# GBprinter-D1-Shield.net
KiCad netlist of a schematic drawn in EAGLE
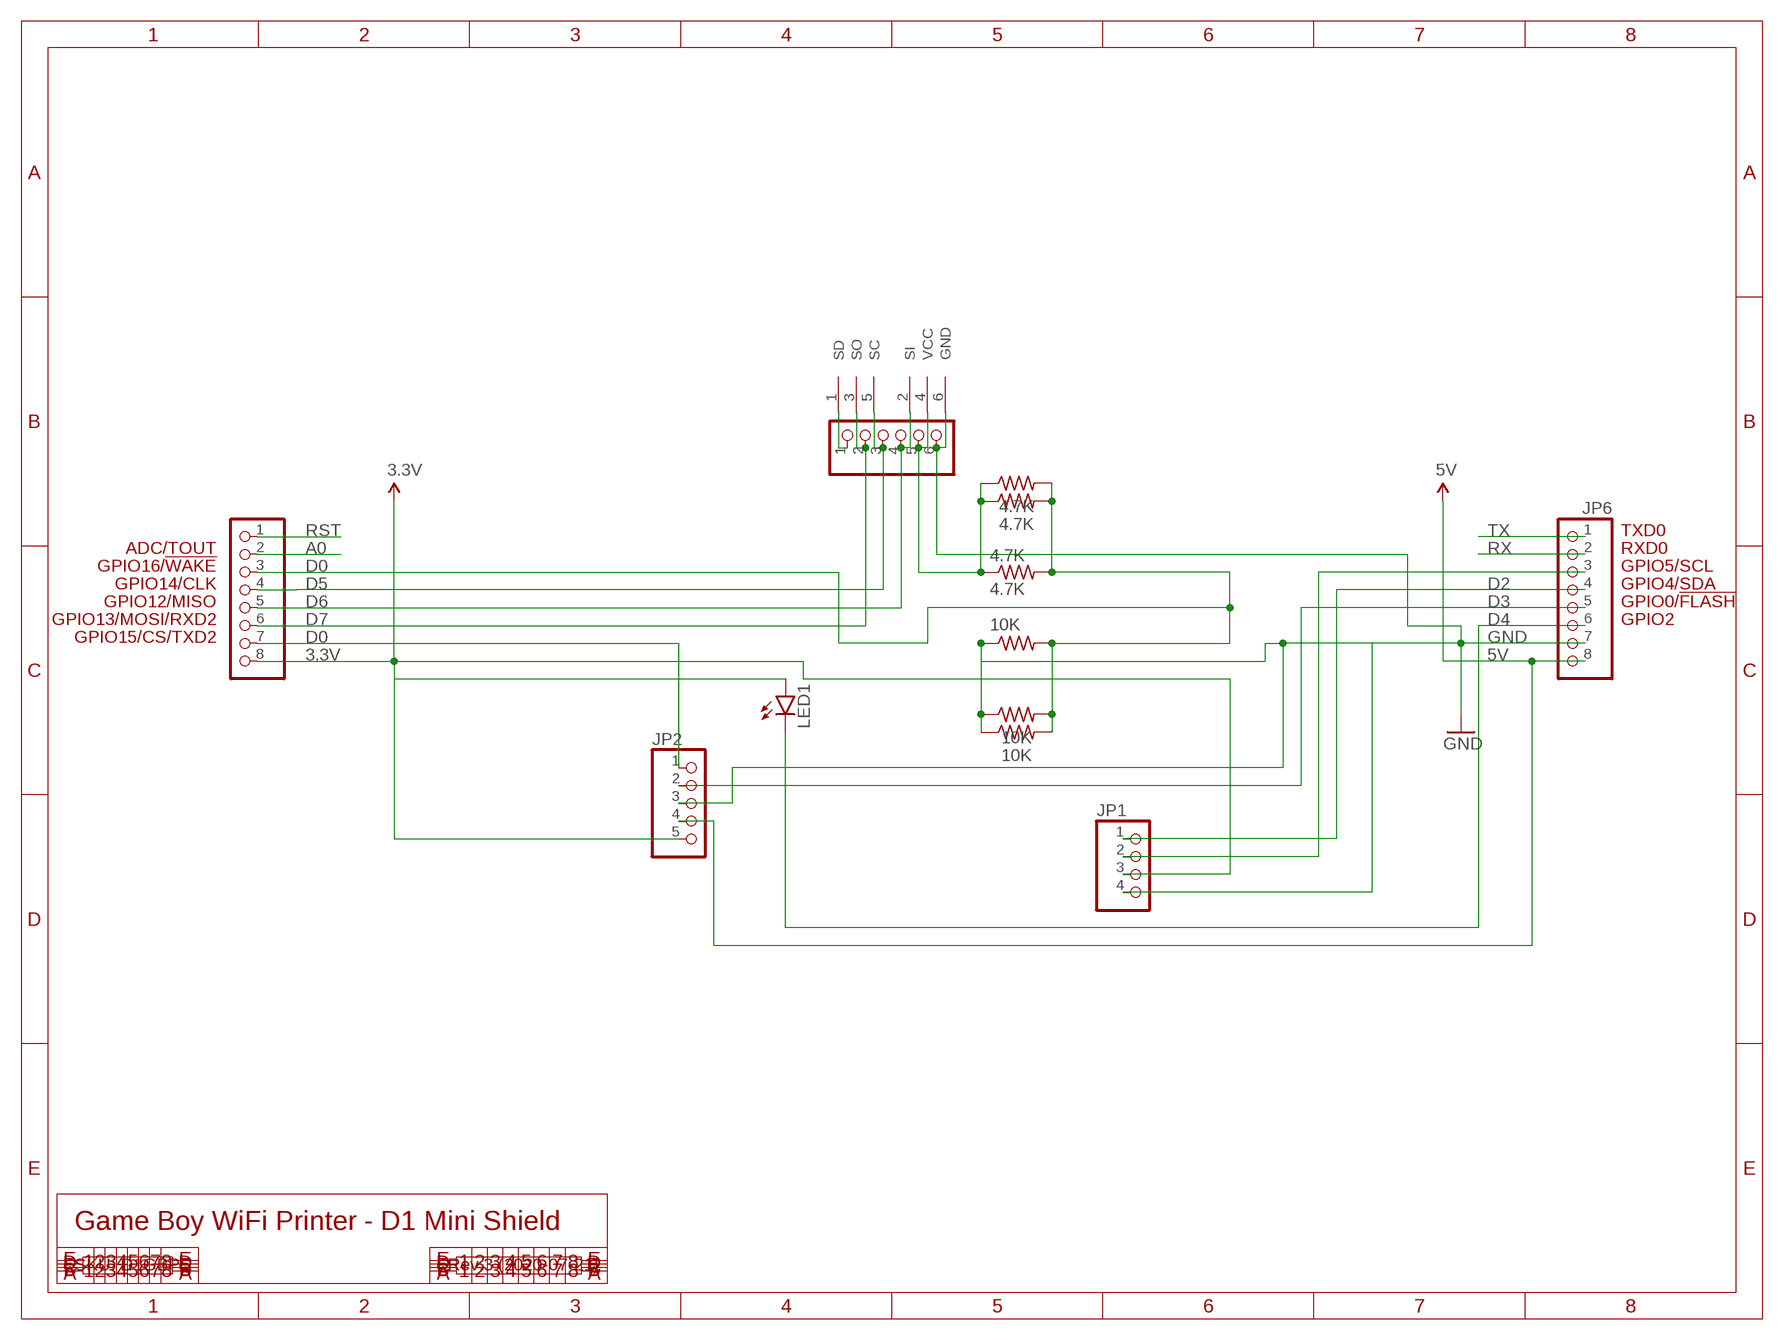
[diagram p0: schematic, sheet 1]

(export (version "E")
  (design (tool "Eeschema 10.0.6"))
  (components
    (comp (ref "4.7K")
      (value "4.7K")
      (footprint "eagle-import:0207_10")
      (libsource (lib "eagle-import") (part "R-US_0207/10"))
    )
    (comp (ref "10K")
      (value "10K")
      (footprint "eagle-import:0207_10")
      (libsource (lib "eagle-import") (part "R-US_0207/10"))
    )
    (comp (ref "JP1")
      (value "PINHD-1X4/OCT")
      (footprint "eagle-import:1X04_OCT")
      (libsource (lib "eagle-import") (part "PINHD-1X4/OCT"))
    )
    (comp (ref "JP2")
      (value "PINHD-1X5/OCT")
      (footprint "eagle-import:1X05_OCT")
      (libsource (lib "eagle-import") (part "PINHD-1X5/OCT"))
    )
    (comp (ref "JP3")
      (value "PINHD-1X8/OCT")
      (footprint "eagle-import:1X08_OCT")
      (libsource (lib "eagle-import") (part "PINHD-1X8/OCT"))
    )
    (comp (ref "JP4")
      (value "PINHD-1X6/OCT")
      (footprint "eagle-import:1X06_OCT")
      (libsource (lib "eagle-import") (part "PINHD-1X6/OCT"))
    )
    (comp (ref "JP6")
      (value "PINHD-1X8/OCT")
      (footprint "eagle-import:1X08_OCT")
      (libsource (lib "eagle-import") (part "PINHD-1X8/OCT"))
    )
    (comp (ref "LED1")
      (value "LED3MM")
      (footprint "eagle-import:LED3MM")
      (libsource (lib "eagle-import") (part "LED3MM"))
    )
    (comp (ref "R1")
      (value "4.7K")
      (footprint "eagle-import:RESC2012X65")
      (libsource (lib "eagle-import") (part "R-USCHIP-0805(2012-METRIC)_"))
    )
    (comp (ref "R2")
      (value "10K")
      (footprint "eagle-import:RESC2012X65")
      (libsource (lib "eagle-import") (part "R-USCHIP-0805(2012-METRIC)_"))
    )
    (comp (ref "R3")
      (value "10K")
      (footprint "eagle-import:RESC2012X65")
      (libsource (lib "eagle-import") (part "R-USCHIP-0805(2012-METRIC)_"))
    )
    (comp (ref "R5")
      (value "4.7K")
      (footprint "eagle-import:RESC2012X65")
      (libsource (lib "eagle-import") (part "R-USCHIP-0805(2012-METRIC)_"))
    )
    (comp (ref "U$2")
      (value "GB-LINK-PADS")
      (footprint "eagle-import:GB-LINK-PCB")
      (libsource (lib "eagle-import") (part "GB-LINK-PADS"))
    )
  )
  (nets
    (net (code "1") (name "/A0") (class "Default")
      (node (ref "JP3") (pin "2") (pinfunction "2_2") (pintype "passive"))
    )
    (net (code "2") (name "/D0") (class "Default")
      (node (ref "10K") (pin "2") (pinfunction "2_2") (pintype "passive"))
      (node (ref "4.7K") (pin "2") (pinfunction "2_2") (pintype "passive"))
      (node (ref "JP3") (pin "3") (pinfunction "3_3") (pintype "passive"))
      (node (ref "R1") (pin "2") (pinfunction "2_2") (pintype "passive"))
      (node (ref "R2") (pin "2") (pinfunction "2_2") (pintype "passive"))
      (node (ref "R3") (pin "2") (pinfunction "2_2") (pintype "passive"))
      (node (ref "R5") (pin "2") (pinfunction "2_2") (pintype "passive"))
    )
    (net (code "3") (name "/D2") (class "Default")
      (node (ref "JP1") (pin "1") (pinfunction "1_1") (pintype "passive"))
      (node (ref "JP6") (pin "4") (pinfunction "4_4") (pintype "passive"))
    )
    (net (code "4") (name "/D3") (class "Default")
      (node (ref "JP2") (pin "2") (pinfunction "2_2") (pintype "passive"))
      (node (ref "JP6") (pin "5") (pinfunction "5_5") (pintype "passive"))
    )
    (net (code "5") (name "/D4") (class "Default")
      (node (ref "JP6") (pin "6") (pinfunction "6_6") (pintype "passive"))
      (node (ref "LED1") (pin "K") (pinfunction "C_K") (pintype "passive"))
    )
    (net (code "6") (name "/D5") (class "Default")
      (node (ref "JP3") (pin "4") (pinfunction "4_4") (pintype "passive"))
      (node (ref "JP4") (pin "3") (pinfunction "3_3") (pintype "passive"))
      (node (ref "U$2") (pin "5") (pinfunction "SC_5") (pintype "bidirectional"))
    )
    (net (code "7") (name "/D6") (class "Default")
      (node (ref "JP3") (pin "5") (pinfunction "5_5") (pintype "passive"))
      (node (ref "JP4") (pin "4") (pinfunction "4_4") (pintype "passive"))
      (node (ref "U$2") (pin "2") (pinfunction "SI_2") (pintype "bidirectional"))
    )
    (net (code "8") (name "/D7") (class "Default")
      (node (ref "JP3") (pin "6") (pinfunction "6_6") (pintype "passive"))
      (node (ref "JP4") (pin "2") (pinfunction "2_2") (pintype "passive"))
      (node (ref "U$2") (pin "3") (pinfunction "SO_3") (pintype "bidirectional"))
    )
    (net (code "9") (name "/RST") (class "Default")
      (node (ref "JP3") (pin "1") (pinfunction "1_1") (pintype "passive"))
    )
    (net (code "10") (name "/RX") (class "Default")
      (node (ref "JP6") (pin "2") (pinfunction "2_2") (pintype "passive"))
    )
    (net (code "11") (name "/TX") (class "Default")
      (node (ref "JP6") (pin "1") (pinfunction "1_1") (pintype "passive"))
    )
    (net (code "12") (name "3.3V") (class "Default")
      (node (ref "JP1") (pin "3") (pinfunction "3_3") (pintype "passive"))
      (node (ref "JP2") (pin "5") (pinfunction "5_5") (pintype "passive"))
      (node (ref "JP3") (pin "8") (pinfunction "8_8") (pintype "passive"))
      (node (ref "LED1") (pin "A") (pinfunction "A_A") (pintype "passive"))
    )
    (net (code "13") (name "5V") (class "Default")
      (node (ref "JP2") (pin "4") (pinfunction "4_4") (pintype "passive"))
      (node (ref "JP6") (pin "8") (pinfunction "8_8") (pintype "passive"))
    )
    (net (code "14") (name "GND") (class "Default")
      (node (ref "10K") (pin "1") (pinfunction "1_1") (pintype "passive"))
      (node (ref "JP1") (pin "4") (pinfunction "4_4") (pintype "passive"))
      (node (ref "JP2") (pin "3") (pinfunction "3_3") (pintype "passive"))
      (node (ref "JP4") (pin "6") (pinfunction "6_6") (pintype "passive"))
      (node (ref "JP6") (pin "7") (pinfunction "7_7") (pintype "passive"))
      (node (ref "R2") (pin "1") (pinfunction "1_1") (pintype "passive"))
      (node (ref "R3") (pin "1") (pinfunction "1_1") (pintype "passive"))
      (node (ref "U$2") (pin "6") (pinfunction "GND_6") (pintype "bidirectional"))
    )
    (net (code "15") (name "Net-(JP1-Pad2)") (class "Default")
      (node (ref "JP1") (pin "2") (pinfunction "2_2") (pintype "passive"))
      (node (ref "JP6") (pin "3") (pinfunction "3_3") (pintype "passive"))
    )
    (net (code "16") (name "Net-(JP2-Pad1)") (class "Default")
      (node (ref "JP2") (pin "1") (pinfunction "1_1") (pintype "passive"))
      (node (ref "JP3") (pin "7") (pinfunction "7_7") (pintype "passive"))
    )
    (net (code "17") (name "Net-(U$2-SD)") (class "Default")
      (node (ref "JP4") (pin "1") (pinfunction "1_1") (pintype "passive"))
      (node (ref "U$2") (pin "1") (pinfunction "SD_1") (pintype "bidirectional"))
    )
    (net (code "18") (name "Net-(U$2-VCC)") (class "Default")
      (node (ref "4.7K") (pin "1") (pinfunction "1_1") (pintype "passive"))
      (node (ref "JP4") (pin "5") (pinfunction "5_5") (pintype "passive"))
      (node (ref "R1") (pin "1") (pinfunction "1_1") (pintype "passive"))
      (node (ref "R5") (pin "1") (pinfunction "1_1") (pintype "passive"))
      (node (ref "U$2") (pin "4") (pinfunction "VCC_4") (pintype "bidirectional"))
    )
  )
)
